# draft4_4lyr_autoroute.net
KiCad netlist of a schematic drawn in EAGLE
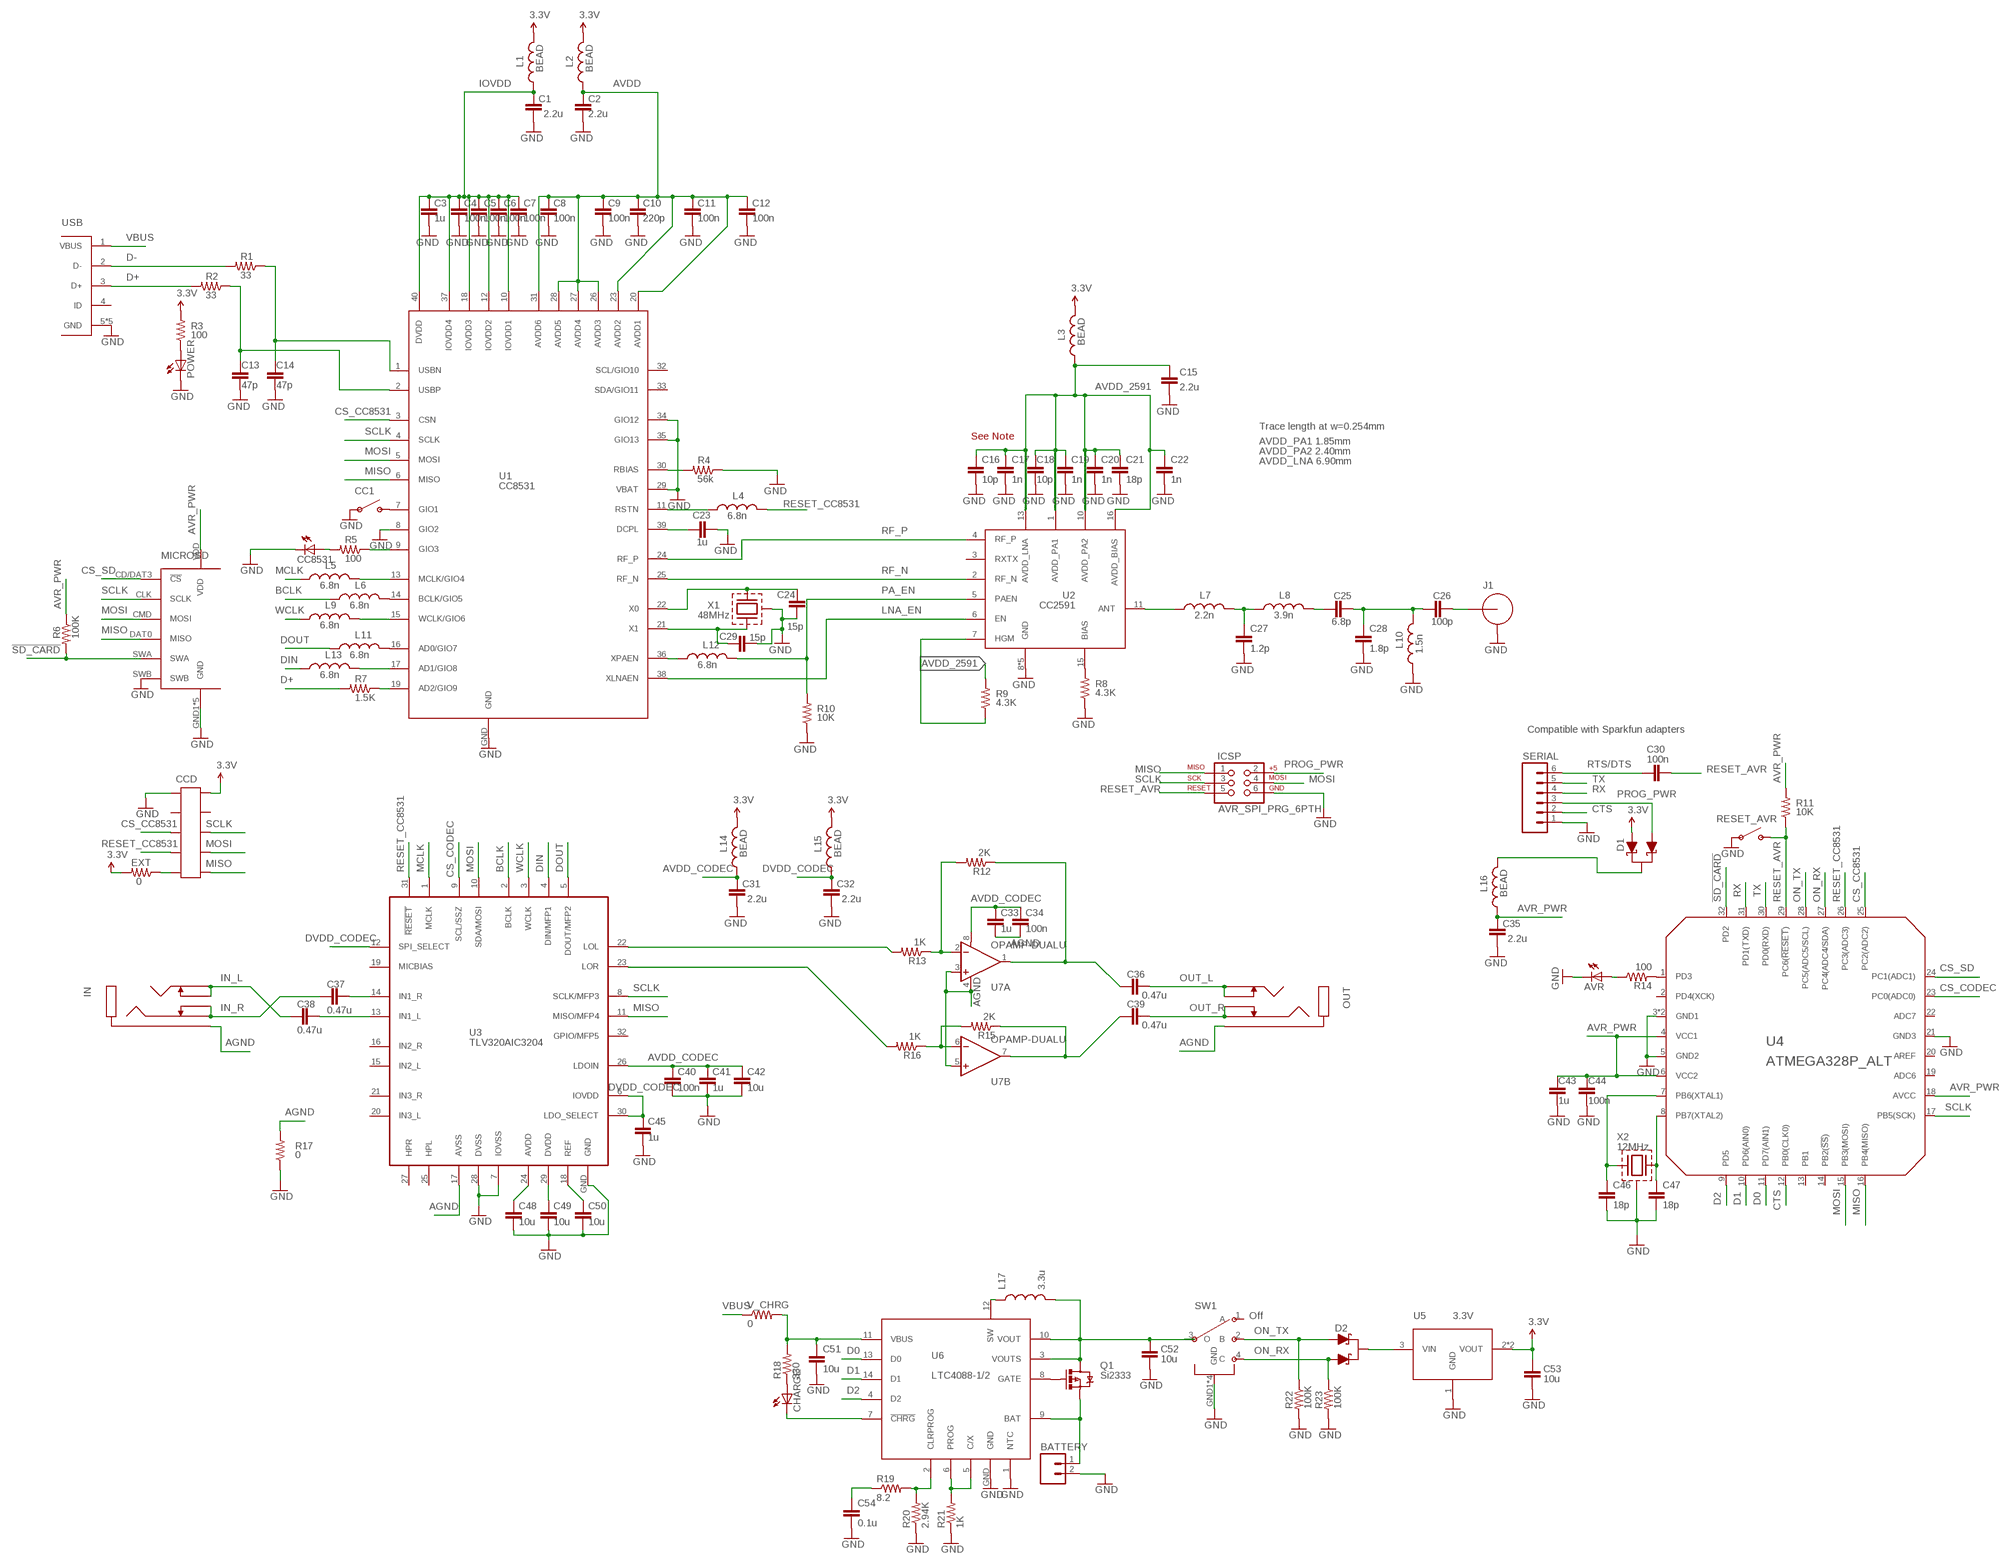
[diagram p0: schematic, sheet 1]

(export (version "E")
  (design (tool "Eeschema 10.0.6"))
  (components
    (comp (ref "AVR")
      (value "LED1206")
      (footprint "eagle-import:LED-1206")
      (libsource (lib "eagle-import") (part "LED1206"))
    )
    (comp (ref "BATTERY")
      (value "M02-JST-2MM-SMT")
      (footprint "eagle-import:JST-2-SMD")
      (libsource (lib "eagle-import") (part "M02-JST-2MM-SMT"))
    )
    (comp (ref "C1")
      (value "2.2u")
      (footprint "eagle-import:C0603")
      (libsource (lib "eagle-import") (part "rcl_C-EUC0603"))
    )
    (comp (ref "C2")
      (value "2.2u")
      (footprint "eagle-import:C0603")
      (libsource (lib "eagle-import") (part "rcl_C-EUC0603"))
    )
    (comp (ref "C3")
      (value "1u")
      (footprint "eagle-import:C0603")
      (libsource (lib "eagle-import") (part "rcl_C-EUC0603"))
    )
    (comp (ref "C4")
      (value "100n")
      (footprint "eagle-import:C0603")
      (libsource (lib "eagle-import") (part "rcl_C-EUC0603"))
    )
    (comp (ref "C5")
      (value "100n")
      (footprint "eagle-import:C0603")
      (libsource (lib "eagle-import") (part "rcl_C-EUC0603"))
    )
    (comp (ref "C6")
      (value "100n")
      (footprint "eagle-import:C0603")
      (libsource (lib "eagle-import") (part "rcl_C-EUC0603"))
    )
    (comp (ref "C7")
      (value "100n")
      (footprint "eagle-import:C0603")
      (libsource (lib "eagle-import") (part "rcl_C-EUC0603"))
    )
    (comp (ref "C8")
      (value "100n")
      (footprint "eagle-import:C0603")
      (libsource (lib "eagle-import") (part "rcl_C-EUC0603"))
    )
    (comp (ref "C9")
      (value "100n")
      (footprint "eagle-import:C0603")
      (libsource (lib "eagle-import") (part "rcl_C-EUC0603"))
    )
    (comp (ref "C10")
      (value "220p")
      (footprint "eagle-import:C0603")
      (libsource (lib "eagle-import") (part "rcl_C-EUC0603"))
    )
    (comp (ref "C11")
      (value "100n")
      (footprint "eagle-import:C0603")
      (libsource (lib "eagle-import") (part "rcl_C-EUC0603"))
    )
    (comp (ref "C12")
      (value "100n")
      (footprint "eagle-import:C0603")
      (libsource (lib "eagle-import") (part "rcl_C-EUC0603"))
    )
    (comp (ref "C13")
      (value "47p")
      (footprint "eagle-import:C0603")
      (libsource (lib "eagle-import") (part "rcl_C-EUC0603"))
    )
    (comp (ref "C14")
      (value "47p")
      (footprint "eagle-import:C0603")
      (libsource (lib "eagle-import") (part "rcl_C-EUC0603"))
    )
    (comp (ref "C15")
      (value "2.2u")
      (footprint "eagle-import:C0603")
      (libsource (lib "eagle-import") (part "rcl_C-EUC0603"))
    )
    (comp (ref "C16")
      (value "10p")
      (footprint "eagle-import:C0603")
      (libsource (lib "eagle-import") (part "rcl_C-EUC0603"))
    )
    (comp (ref "C17")
      (value "1n")
      (footprint "eagle-import:C0603")
      (libsource (lib "eagle-import") (part "rcl_C-EUC0603"))
    )
    (comp (ref "C18")
      (value "10p")
      (footprint "eagle-import:C0603")
      (libsource (lib "eagle-import") (part "rcl_C-EUC0603"))
    )
    (comp (ref "C19")
      (value "1n")
      (footprint "eagle-import:C0603")
      (libsource (lib "eagle-import") (part "rcl_C-EUC0603"))
    )
    (comp (ref "C20")
      (value "1n")
      (footprint "eagle-import:C0603")
      (libsource (lib "eagle-import") (part "rcl_C-EUC0603"))
    )
    (comp (ref "C21")
      (value "18p")
      (footprint "eagle-import:C0603")
      (libsource (lib "eagle-import") (part "rcl_C-EUC0603"))
    )
    (comp (ref "C22")
      (value "1n")
      (footprint "eagle-import:C0603")
      (libsource (lib "eagle-import") (part "rcl_C-EUC0603"))
    )
    (comp (ref "C23")
      (value "1u")
      (footprint "eagle-import:C0603")
      (libsource (lib "eagle-import") (part "rcl_C-EUC0603"))
    )
    (comp (ref "C24")
      (value "15p")
      (footprint "eagle-import:C0603")
      (libsource (lib "eagle-import") (part "rcl_C-EUC0603"))
    )
    (comp (ref "C25")
      (value "6.8p")
      (footprint "eagle-import:C0603")
      (libsource (lib "eagle-import") (part "rcl_C-EUC0603"))
    )
    (comp (ref "C26")
      (value "100p")
      (footprint "eagle-import:C0603")
      (libsource (lib "eagle-import") (part "rcl_C-EUC0603"))
    )
    (comp (ref "C27")
      (value "1.2p")
      (footprint "eagle-import:C0603")
      (libsource (lib "eagle-import") (part "rcl_C-EUC0603"))
    )
    (comp (ref "C28")
      (value "1.8p")
      (footprint "eagle-import:C0603")
      (libsource (lib "eagle-import") (part "rcl_C-EUC0603"))
    )
    (comp (ref "C29")
      (value "15p")
      (footprint "eagle-import:C0603")
      (libsource (lib "eagle-import") (part "rcl_C-EUC0603"))
    )
    (comp (ref "C30")
      (value "100n")
      (footprint "eagle-import:C0603")
      (libsource (lib "eagle-import") (part "rcl_C-EUC0603"))
    )
    (comp (ref "C31")
      (value "2.2u")
      (footprint "eagle-import:C0603")
      (libsource (lib "eagle-import") (part "rcl_C-EUC0603"))
    )
    (comp (ref "C32")
      (value "2.2u")
      (footprint "eagle-import:C0603")
      (libsource (lib "eagle-import") (part "rcl_C-EUC0603"))
    )
    (comp (ref "C33")
      (value "1u")
      (footprint "eagle-import:C0603")
      (libsource (lib "eagle-import") (part "rcl_C-EUC0603"))
    )
    (comp (ref "C34")
      (value "100n")
      (footprint "eagle-import:C0603")
      (libsource (lib "eagle-import") (part "rcl_C-EUC0603"))
    )
    (comp (ref "C35")
      (value "2.2u")
      (footprint "eagle-import:C0603")
      (libsource (lib "eagle-import") (part "rcl_C-EUC0603"))
    )
    (comp (ref "C36")
      (value "0.47u")
      (footprint "eagle-import:C0603")
      (libsource (lib "eagle-import") (part "rcl_C-EUC0603"))
    )
    (comp (ref "C37")
      (value "0.47u")
      (footprint "eagle-import:C0603")
      (libsource (lib "eagle-import") (part "rcl_C-EUC0603"))
    )
    (comp (ref "C38")
      (value "0.47u")
      (footprint "eagle-import:C0603")
      (libsource (lib "eagle-import") (part "rcl_C-EUC0603"))
    )
    (comp (ref "C39")
      (value "0.47u")
      (footprint "eagle-import:C0603")
      (libsource (lib "eagle-import") (part "rcl_C-EUC0603"))
    )
    (comp (ref "C40")
      (value "100n")
      (footprint "eagle-import:C0603")
      (libsource (lib "eagle-import") (part "rcl_C-EUC0603"))
    )
    (comp (ref "C41")
      (value "1u")
      (footprint "eagle-import:C0603")
      (libsource (lib "eagle-import") (part "rcl_C-EUC0603"))
    )
    (comp (ref "C42")
      (value "10u")
      (footprint "eagle-import:C0603")
      (libsource (lib "eagle-import") (part "rcl_C-EUC0603"))
    )
    (comp (ref "C43")
      (value "1u")
      (footprint "eagle-import:C0603")
      (libsource (lib "eagle-import") (part "rcl_C-EUC0603"))
    )
    (comp (ref "C44")
      (value "100n")
      (footprint "eagle-import:C0603")
      (libsource (lib "eagle-import") (part "rcl_C-EUC0603"))
    )
    (comp (ref "C45")
      (value "1u")
      (footprint "eagle-import:C0603")
      (libsource (lib "eagle-import") (part "rcl_C-EUC0603"))
    )
    (comp (ref "C46")
      (value "18p")
      (footprint "eagle-import:C0603")
      (libsource (lib "eagle-import") (part "C-EUC0603"))
    )
    (comp (ref "C47")
      (value "18p")
      (footprint "eagle-import:C0603")
      (libsource (lib "eagle-import") (part "C-EUC0603"))
    )
    (comp (ref "C48")
      (value "10u")
      (footprint "eagle-import:C0603")
      (libsource (lib "eagle-import") (part "rcl_C-EUC0603"))
    )
    (comp (ref "C49")
      (value "10u")
      (footprint "eagle-import:C0603")
      (libsource (lib "eagle-import") (part "rcl_C-EUC0603"))
    )
    (comp (ref "C50")
      (value "10u")
      (footprint "eagle-import:C0603")
      (libsource (lib "eagle-import") (part "rcl_C-EUC0603"))
    )
    (comp (ref "C51")
      (value "10u")
      (footprint "eagle-import:C0603")
      (libsource (lib "eagle-import") (part "C-EUC0603"))
    )
    (comp (ref "C52")
      (value "10u")
      (footprint "eagle-import:C0603")
      (libsource (lib "eagle-import") (part "rcl_C-EUC0603"))
    )
    (comp (ref "C53")
      (value "10u")
      (footprint "eagle-import:C0603")
      (libsource (lib "eagle-import") (part "rcl_C-EUC0603"))
    )
    (comp (ref "C54")
      (value "0.1u")
      (footprint "eagle-import:C0603")
      (libsource (lib "eagle-import") (part "C-EUC0603"))
    )
    (comp (ref "CC1")
      (value "SPST-SMD")
      (footprint "eagle-import:TACT_SW")
      (libsource (lib "eagle-import") (part "SPST-SMD"))
    )
    (comp (ref "CC8531")
      (value "LED1206")
      (footprint "eagle-import:LED-1206")
      (libsource (lib "eagle-import") (part "LED1206"))
    )
    (comp (ref "CCD")
      (value "HEADER-10P-PTH-MALE")
      (footprint "eagle-import:2X5")
      (libsource (lib "eagle-import") (part "HEADER-10P-PTH-MALE"))
    )
    (comp (ref "CHARGE")
      (value "LED1206")
      (footprint "eagle-import:LED-1206")
      (libsource (lib "eagle-import") (part "LED1206"))
    )
    (comp (ref "D1")
      (value "DUAL_SCHOTTKY")
      (footprint "eagle-import:SOT-23")
      (libsource (lib "eagle-import") (part "DUAL_SCHOTTKY"))
    )
    (comp (ref "D2")
      (value "DUAL_SCHOTTKY")
      (footprint "eagle-import:SOT-23")
      (libsource (lib "eagle-import") (part "DUAL_SCHOTTKY"))
    )
    (comp (ref "EXT")
      (value "0")
      (footprint "eagle-import:R0603")
      (libsource (lib "eagle-import") (part "rcl_R-US_R0603"))
    )
    (comp (ref "ICSP")
      (value "AVR_SPI_PRG_6PTH")
      (footprint "eagle-import:2X3")
      (libsource (lib "eagle-import") (part "AVR_SPI_PRG_6PTH"))
    )
    (comp (ref "IN")
      (value "PHONE_SW")
      (footprint "eagle-import:35RAPC4BV4")
      (libsource (lib "eagle-import") (part "PHONE_SW"))
    )
    (comp (ref "J1")
      (value "SMA")
      (footprint "eagle-import:CONSMA003.031")
      (libsource (lib "eagle-import") (part "SMA"))
    )
    (comp (ref "L1")
      (value "BEAD")
      (footprint "eagle-import:0603")
      (libsource (lib "eagle-import") (part "INDUCTOR0603"))
    )
    (comp (ref "L2")
      (value "BEAD")
      (footprint "eagle-import:0603")
      (libsource (lib "eagle-import") (part "INDUCTOR0603"))
    )
    (comp (ref "L3")
      (value "BEAD")
      (footprint "eagle-import:0603")
      (libsource (lib "eagle-import") (part "INDUCTOR0603"))
    )
    (comp (ref "L4")
      (value "6.8n")
      (footprint "eagle-import:0603")
      (libsource (lib "eagle-import") (part "INDUCTOR0603"))
    )
    (comp (ref "L5")
      (value "6.8n")
      (footprint "eagle-import:0603")
      (libsource (lib "eagle-import") (part "INDUCTOR0603"))
    )
    (comp (ref "L6")
      (value "6.8n")
      (footprint "eagle-import:0603")
      (libsource (lib "eagle-import") (part "INDUCTOR0603"))
    )
    (comp (ref "L7")
      (value "2.2n")
      (footprint "eagle-import:0603")
      (libsource (lib "eagle-import") (part "INDUCTOR0603"))
    )
    (comp (ref "L8")
      (value "3.9n")
      (footprint "eagle-import:0603")
      (libsource (lib "eagle-import") (part "INDUCTOR0603"))
    )
    (comp (ref "L9")
      (value "6.8n")
      (footprint "eagle-import:0603")
      (libsource (lib "eagle-import") (part "INDUCTOR0603"))
    )
    (comp (ref "L10")
      (value "1.5n")
      (footprint "eagle-import:0603")
      (libsource (lib "eagle-import") (part "INDUCTOR0603"))
    )
    (comp (ref "L11")
      (value "6.8n")
      (footprint "eagle-import:0603")
      (libsource (lib "eagle-import") (part "INDUCTOR0603"))
    )
    (comp (ref "L12")
      (value "6.8n")
      (footprint "eagle-import:0603")
      (libsource (lib "eagle-import") (part "INDUCTOR0603"))
    )
    (comp (ref "L13")
      (value "6.8n")
      (footprint "eagle-import:0603")
      (libsource (lib "eagle-import") (part "INDUCTOR0603"))
    )
    (comp (ref "L14")
      (value "BEAD")
      (footprint "eagle-import:0603")
      (libsource (lib "eagle-import") (part "INDUCTOR0603"))
    )
    (comp (ref "L15")
      (value "BEAD")
      (footprint "eagle-import:0603")
      (libsource (lib "eagle-import") (part "INDUCTOR0603"))
    )
    (comp (ref "L16")
      (value "BEAD")
      (footprint "eagle-import:0603")
      (libsource (lib "eagle-import") (part "INDUCTOR0603"))
    )
    (comp (ref "L17")
      (value "3.3u")
      (footprint "eagle-import:IFSC-1111AB-01")
      (libsource (lib "eagle-import") (part "IFSC-1111AB-01"))
    )
    (comp (ref "MICROSD")
      (value "MICROSD104031-0811")
      (footprint "eagle-import:MOLEX_104031-0811")
      (libsource (lib "eagle-import") (part "MICROSD104031-0811"))
    )
    (comp (ref "OUT")
      (value "PHONE_SW")
      (footprint "eagle-import:35RAPC4BV4")
      (libsource (lib "eagle-import") (part "PHONE_SW"))
    )
    (comp (ref "POWER")
      (value "LED1206")
      (footprint "eagle-import:LED-1206")
      (libsource (lib "eagle-import") (part "LED1206"))
    )
    (comp (ref "Q1")
      (value "Si2333")
      (footprint "eagle-import:SOT23-3")
      (libsource (lib "eagle-import") (part "MOSFET-PCHANNELSMD"))
    )
    (comp (ref "R1")
      (value "33")
      (footprint "eagle-import:R0603")
      (libsource (lib "eagle-import") (part "rcl_R-US_R0603"))
    )
    (comp (ref "R2")
      (value "33")
      (footprint "eagle-import:R0603")
      (libsource (lib "eagle-import") (part "rcl_R-US_R0603"))
    )
    (comp (ref "R3")
      (value "100")
      (footprint "eagle-import:R0603")
      (libsource (lib "eagle-import") (part "rcl_R-US_R0603"))
    )
    (comp (ref "R4")
      (value "56k")
      (footprint "eagle-import:R0603")
      (libsource (lib "eagle-import") (part "rcl_R-US_R0603"))
    )
    (comp (ref "R5")
      (value "100")
      (footprint "eagle-import:R0603")
      (libsource (lib "eagle-import") (part "rcl_R-US_R0603"))
    )
    (comp (ref "R6")
      (value "100K")
      (footprint "eagle-import:R0603")
      (libsource (lib "eagle-import") (part "rcl_R-US_R0603"))
    )
    (comp (ref "R7")
      (value "1.5K")
      (footprint "eagle-import:R0603")
      (libsource (lib "eagle-import") (part "rcl_R-US_R0603"))
    )
    (comp (ref "R8")
      (value "4.3K")
      (footprint "eagle-import:R0603")
      (libsource (lib "eagle-import") (part "rcl_R-US_R0603"))
    )
    (comp (ref "R9")
      (value "4.3K")
      (footprint "eagle-import:R0603")
      (libsource (lib "eagle-import") (part "rcl_R-US_R0603"))
    )
    (comp (ref "R10")
      (value "10K")
      (footprint "eagle-import:R0603")
      (libsource (lib "eagle-import") (part "rcl_R-US_R0603"))
    )
    (comp (ref "R11")
      (value "10K")
      (footprint "eagle-import:R0603")
      (libsource (lib "eagle-import") (part "rcl_R-US_R0603"))
    )
    (comp (ref "R12")
      (value "2K")
      (footprint "eagle-import:R0603")
      (libsource (lib "eagle-import") (part "R-US_R0603"))
    )
    (comp (ref "R13")
      (value "1K")
      (footprint "eagle-import:R0603")
      (libsource (lib "eagle-import") (part "R-US_R0603"))
    )
    (comp (ref "R14")
      (value "100")
      (footprint "eagle-import:R0603")
      (libsource (lib "eagle-import") (part "rcl_R-US_R0603"))
    )
    (comp (ref "R15")
      (value "2K")
      (footprint "eagle-import:R0603")
      (libsource (lib "eagle-import") (part "R-US_R0603"))
    )
    (comp (ref "R16")
      (value "1K")
      (footprint "eagle-import:R0603")
      (libsource (lib "eagle-import") (part "R-US_R0603"))
    )
    (comp (ref "R17")
      (value "0")
      (footprint "eagle-import:R0603")
      (libsource (lib "eagle-import") (part "rcl_R-US_R0603"))
    )
    (comp (ref "R18")
      (value "330")
      (footprint "eagle-import:R0603")
      (libsource (lib "eagle-import") (part "R-US_R0603"))
    )
    (comp (ref "R19")
      (value "8.2")
      (footprint "eagle-import:R0603")
      (libsource (lib "eagle-import") (part "R-US_R0603"))
    )
    (comp (ref "R20")
      (value "2.94K")
      (footprint "eagle-import:R0603")
      (libsource (lib "eagle-import") (part "R-US_R0603"))
    )
    (comp (ref "R21")
      (value "1K")
      (footprint "eagle-import:R0603")
      (libsource (lib "eagle-import") (part "R-US_R0603"))
    )
    (comp (ref "R22")
      (value "100K")
      (footprint "eagle-import:R0603")
      (libsource (lib "eagle-import") (part "rcl_R-US_R0603"))
    )
    (comp (ref "R23")
      (value "100K")
      (footprint "eagle-import:R0603")
      (libsource (lib "eagle-import") (part "rcl_R-US_R0603"))
    )
    (comp (ref "RESET_AVR")
      (value "SPST-SMD")
      (footprint "eagle-import:TACT_SW")
      (libsource (lib "eagle-import") (part "SPST-SMD"))
    )
    (comp (ref "SERIAL")
      (value "M06SIP")
      (footprint "eagle-import:1X06")
      (libsource (lib "eagle-import") (part "M06SIP"))
    )
    (comp (ref "SW1")
      (value "SP3T-SSSS812201")
      (footprint "eagle-import:SSSS812201")
      (libsource (lib "eagle-import") (part "SP3T-SSSS812201"))
    )
    (comp (ref "U1")
      (value "CC8531")
      (footprint "eagle-import:S-PVQFN-N40")
      (libsource (lib "eagle-import") (part "CC8531"))
    )
    (comp (ref "U2")
      (value "CC2591")
      (footprint "eagle-import:S-PVQFN-N16")
      (libsource (lib "eagle-import") (part "CC2591"))
    )
    (comp (ref "U3")
      (value "TLV320AIC3204")
      (footprint "eagle-import:S-PVQFN-N32")
      (libsource (lib "eagle-import") (part "TLV320AIC3204"))
    )
    (comp (ref "U4")
      (value "ATMEGA328P_ALT")
      (footprint "eagle-import:S-PQFP-N32")
      (libsource (lib "eagle-import") (part "ATMEGA328P_ALT"))
    )
    (comp (ref "U5")
      (value "3.3V")
      (footprint "eagle-import:SOT-223")
      (libsource (lib "eagle-import") (part "NX1117C"))
    )
    (comp (ref "U6")
      (value "LTC4088-1/2")
      (footprint "eagle-import:DFN-14")
      (libsource (lib "eagle-import") (part "LTC4088-1/2"))
    )
    (comp (ref "U7")
      (value "OPAMP-DUALU")
      (footprint "eagle-import:SO08")
      (libsource (lib "eagle-import") (part "OPAMP-DUALU"))
    )
    (comp (ref "USB")
      (value "USB_MICRO_AB")
      (footprint "eagle-import:USB_MICRO_AB")
      (libsource (lib "eagle-import") (part "USB_MICRO_AB"))
    )
    (comp (ref "V_CHRG")
      (value "0")
      (footprint "eagle-import:R0603")
      (libsource (lib "eagle-import") (part "R-US_R0603"))
    )
    (comp (ref "X1")
      (value "48MHz")
      (footprint "eagle-import:ABM3C")
      (libsource (lib "eagle-import") (part "XTAL-ABRACONABM3C"))
    )
    (comp (ref "X2")
      (value "12MHz")
      (footprint "eagle-import:ABM8G")
      (libsource (lib "eagle-import") (part "XTAL-ABRACONABM8G"))
    )
  )
  (nets
    (net (code "1") (name "/AGND") (class "Default")
      (node (ref "C33") (pin "2") (pinfunction "2_2") (pintype "passive"))
      (node (ref "C34") (pin "2") (pinfunction "2_2") (pintype "passive"))
      (node (ref "IN") (pin "1") (pinfunction "GND_1") (pintype "bidirectional"))
      (node (ref "OUT") (pin "1") (pinfunction "GND_1") (pintype "bidirectional"))
      (node (ref "R17") (pin "2") (pinfunction "2_2") (pintype "passive"))
      (node (ref "U3") (pin "17") (pinfunction "AVSS_17") (pintype "bidirectional"))
      (node (ref "U7") (pin "3") (pinfunction "+IN_3") (pintype "input"))
      (node (ref "U7") (pin "4") (pinfunction "V-_4") (pintype "power_in"))
      (node (ref "U7") (pin "5") (pinfunction "+IN_5") (pintype "input"))
    )
    (net (code "2") (name "/AVDD") (class "Default")
      (node (ref "C10") (pin "1") (pinfunction "1_1") (pintype "passive"))
      (node (ref "C11") (pin "1") (pinfunction "1_1") (pintype "passive"))
      (node (ref "C12") (pin "1") (pinfunction "1_1") (pintype "passive"))
      (node (ref "C2") (pin "1") (pinfunction "1_1") (pintype "passive"))
      (node (ref "C8") (pin "1") (pinfunction "1_1") (pintype "passive"))
      (node (ref "C9") (pin "1") (pinfunction "1_1") (pintype "passive"))
      (node (ref "L2") (pin "1") (pinfunction "1_1") (pintype "passive"))
      (node (ref "U1") (pin "20") (pinfunction "AVDD1_20") (pintype "bidirectional"))
      (node (ref "U1") (pin "23") (pinfunction "AVDD2_23") (pintype "bidirectional"))
      (node (ref "U1") (pin "26") (pinfunction "AVDD3_26") (pintype "bidirectional"))
      (node (ref "U1") (pin "27") (pinfunction "AVDD4_27") (pintype "bidirectional"))
      (node (ref "U1") (pin "28") (pinfunction "AVDD5_28") (pintype "bidirectional"))
      (node (ref "U1") (pin "31") (pinfunction "AVDD6_31") (pintype "bidirectional"))
    )
    (net (code "3") (name "/AVDD_CODEC") (class "Default")
      (node (ref "C31") (pin "1") (pinfunction "1_1") (pintype "passive"))
      (node (ref "C33") (pin "1") (pinfunction "1_1") (pintype "passive"))
      (node (ref "C34") (pin "1") (pinfunction "1_1") (pintype "passive"))
      (node (ref "C40") (pin "1") (pinfunction "1_1") (pintype "passive"))
      (node (ref "C41") (pin "1") (pinfunction "1_1") (pintype "passive"))
      (node (ref "C42") (pin "1") (pinfunction "1_1") (pintype "passive"))
      (node (ref "L14") (pin "1") (pinfunction "1_1") (pintype "passive"))
      (node (ref "U3") (pin "26") (pinfunction "LDOIN_26") (pintype "bidirectional"))
      (node (ref "U7") (pin "8") (pinfunction "V+_8") (pintype "power_in"))
    )
    (net (code "4") (name "/AVR_PWR") (class "Default")
      (node (ref "C35") (pin "1") (pinfunction "1_1") (pintype "passive"))
      (node (ref "C43") (pin "1") (pinfunction "1_1") (pintype "passive"))
      (node (ref "C44") (pin "1") (pinfunction "1_1") (pintype "passive"))
      (node (ref "L16") (pin "1") (pinfunction "1_1") (pintype "passive"))
      (node (ref "MICROSD") (pin "VDD") (pinfunction "VDD_VDD") (pintype "bidirectional"))
      (node (ref "R11") (pin "2") (pinfunction "2_2") (pintype "passive"))
      (node (ref "R6") (pin "1") (pinfunction "1_1") (pintype "passive"))
      (node (ref "U4") (pin "18") (pinfunction "AVCC_18") (pintype "bidirectional"))
      (node (ref "U4") (pin "4") (pinfunction "VCC1_4") (pintype "bidirectional"))
      (node (ref "U4") (pin "6") (pinfunction "VCC2_6") (pintype "bidirectional"))
    )
    (net (code "5") (name "/BCLK") (class "Default")
      (node (ref "L6") (pin "1") (pinfunction "1_1") (pintype "passive"))
      (node (ref "U3") (pin "2") (pinfunction "BCLK_2") (pintype "bidirectional"))
    )
    (net (code "6") (name "/CS_CC8531") (class "Default")
      (node (ref "CCD") (pin "5") (pinfunction "5_5") (pintype "bidirectional"))
      (node (ref "U1") (pin "3") (pinfunction "CSN_3") (pintype "bidirectional"))
      (node (ref "U4") (pin "25") (pinfunction "PC2(ADC2)_25") (pintype "bidirectional"))
    )
    (net (code "7") (name "/CS_CODEC") (class "Default")
      (node (ref "U3") (pin "9") (pinfunction "SCL/SSZ_9") (pintype "bidirectional"))
      (node (ref "U4") (pin "23") (pinfunction "PC0(ADC0)_23") (pintype "bidirectional"))
    )
    (net (code "8") (name "/CS_SD") (class "Default")
      (node (ref "MICROSD") (pin "CD/DAT3") (pinfunction "~{CS}_CD/DAT3") (pintype "bidirectional"))
      (node (ref "U4") (pin "24") (pinfunction "PC1(ADC1)_24") (pintype "bidirectional"))
    )
    (net (code "9") (name "/CTS") (class "Default")
      (node (ref "SERIAL") (pin "2") (pinfunction "2_2") (pintype "passive"))
      (node (ref "U4") (pin "12") (pinfunction "PB0(CLK0)_12") (pintype "bidirectional"))
    )
    (net (code "10") (name "/D+") (class "Default")
      (node (ref "R2") (pin "2") (pinfunction "2_2") (pintype "passive"))
      (node (ref "R7") (pin "2") (pinfunction "2_2") (pintype "passive"))
      (node (ref "USB") (pin "3") (pinfunction "D+_3") (pintype "bidirectional"))
    )
    (net (code "11") (name "/D-") (class "Default")
      (node (ref "R1") (pin "2") (pinfunction "2_2") (pintype "passive"))
      (node (ref "USB") (pin "2") (pinfunction "D-_2") (pintype "bidirectional"))
    )
    (net (code "12") (name "/D0") (class "Default")
      (node (ref "U4") (pin "11") (pinfunction "PD7(AIN1)_11") (pintype "bidirectional"))
      (node (ref "U6") (pin "13") (pinfunction "D0_13") (pintype "bidirectional"))
    )
    (net (code "13") (name "/D1") (class "Default")
      (node (ref "U4") (pin "10") (pinfunction "PD6(AIN0)_10") (pintype "bidirectional"))
      (node (ref "U6") (pin "14") (pinfunction "D1_14") (pintype "bidirectional"))
    )
    (net (code "14") (name "/D2") (class "Default")
      (node (ref "U4") (pin "9") (pinfunction "PD5_9") (pintype "bidirectional"))
      (node (ref "U6") (pin "4") (pinfunction "D2_4") (pintype "bidirectional"))
    )
    (net (code "15") (name "/DIN") (class "Default")
      (node (ref "L13") (pin "1") (pinfunction "1_1") (pintype "passive"))
      (node (ref "U3") (pin "4") (pinfunction "DIN/MFP1_4") (pintype "bidirectional"))
    )
    (net (code "16") (name "/DOUT") (class "Default")
      (node (ref "L11") (pin "1") (pinfunction "1_1") (pintype "passive"))
      (node (ref "U3") (pin "5") (pinfunction "DOUT/MFP2_5") (pintype "bidirectional"))
    )
    (net (code "17") (name "/DVDD_CODEC") (class "Default")
      (node (ref "C32") (pin "1") (pinfunction "1_1") (pintype "passive"))
      (node (ref "C45") (pin "1") (pinfunction "1_1") (pintype "passive"))
      (node (ref "L15") (pin "1") (pinfunction "1_1") (pintype "passive"))
      (node (ref "U3") (pin "12") (pinfunction "SPI_SELECT_12") (pintype "bidirectional"))
      (node (ref "U3") (pin "30") (pinfunction "LDO_SELECT_30") (pintype "bidirectional"))
      (node (ref "U3") (pin "6") (pinfunction "IOVDD_6") (pintype "bidirectional"))
    )
    (net (code "18") (name "/IN_L") (class "Default")
      (node (ref "C38") (pin "1") (pinfunction "1_1") (pintype "passive"))
      (node (ref "IN") (pin "2") (pinfunction "L_2") (pintype "bidirectional"))
      (node (ref "IN") (pin "5") (pinfunction "L_SW_5") (pintype "bidirectional"))
    )
    (net (code "19") (name "/IN_R") (class "Default")
      (node (ref "C37") (pin "1") (pinfunction "1_1") (pintype "passive"))
      (node (ref "IN") (pin "3") (pinfunction "R_SW_3") (pintype "bidirectional"))
      (node (ref "IN") (pin "4") (pinfunction "R_4") (pintype "bidirectional"))
    )
    (net (code "20") (name "/IOVDD") (class "Default")
      (node (ref "C1") (pin "1") (pinfunction "1_1") (pintype "passive"))
      (node (ref "C3") (pin "1") (pinfunction "1_1") (pintype "passive"))
      (node (ref "C4") (pin "1") (pinfunction "1_1") (pintype "passive"))
      (node (ref "C5") (pin "1") (pinfunction "1_1") (pintype "passive"))
      (node (ref "C6") (pin "1") (pinfunction "1_1") (pintype "passive"))
      (node (ref "C7") (pin "1") (pinfunction "1_1") (pintype "passive"))
      (node (ref "L1") (pin "1") (pinfunction "1_1") (pintype "passive"))
      (node (ref "U1") (pin "10") (pinfunction "IOVDD1_10") (pintype "bidirectional"))
      (node (ref "U1") (pin "12") (pinfunction "IOVDD2_12") (pintype "bidirectional"))
      (node (ref "U1") (pin "18") (pinfunction "IOVDD3_18") (pintype "bidirectional"))
      (node (ref "U1") (pin "37") (pinfunction "IOVDD4_37") (pintype "bidirectional"))
      (node (ref "U1") (pin "40") (pinfunction "DVDD_40") (pintype "bidirectional"))
    )
    (net (code "21") (name "/LNA_EN") (class "Default")
      (node (ref "U1") (pin "38") (pinfunction "XLNAEN_38") (pintype "bidirectional"))
      (node (ref "U2") (pin "6") (pinfunction "EN_6") (pintype "bidirectional"))
    )
    (net (code "22") (name "/MCLK") (class "Default")
      (node (ref "L5") (pin "1") (pinfunction "1_1") (pintype "passive"))
      (node (ref "U3") (pin "1") (pinfunction "MCLK_1") (pintype "bidirectional"))
    )
    (net (code "23") (name "/MISO") (class "Default")
      (node (ref "CCD") (pin "10") (pinfunction "10_10") (pintype "bidirectional"))
      (node (ref "ICSP") (pin "1") (pinfunction "1_1") (pintype "passive"))
      (node (ref "MICROSD") (pin "DAT0") (pinfunction "MISO_DAT0") (pintype "bidirectional"))
      (node (ref "U1") (pin "6") (pinfunction "MISO_6") (pintype "bidirectional"))
      (node (ref "U3") (pin "11") (pinfunction "MISO/MFP4_11") (pintype "bidirectional"))
      (node (ref "U4") (pin "16") (pinfunction "PB4(MISO)_16") (pintype "bidirectional"))
    )
    (net (code "24") (name "/MOSI") (class "Default")
      (node (ref "CCD") (pin "8") (pinfunction "8_8") (pintype "bidirectional"))
      (node (ref "ICSP") (pin "4") (pinfunction "4_4") (pintype "passive"))
      (node (ref "MICROSD") (pin "CMD") (pinfunction "MOSI_CMD") (pintype "bidirectional"))
      (node (ref "U1") (pin "5") (pinfunction "MOSI_5") (pintype "bidirectional"))
      (node (ref "U3") (pin "10") (pinfunction "SDA/MOSI_10") (pintype "bidirectional"))
      (node (ref "U4") (pin "15") (pinfunction "PB3(MOSI)_15") (pintype "bidirectional"))
    )
    (net (code "25") (name "/ON_RX") (class "Default")
      (node (ref "D2") (pin "2") (pinfunction "A_2") (pintype "passive"))
      (node (ref "R23") (pin "1") (pinfunction "1_1") (pintype "passive"))
      (node (ref "SW1") (pin "4") (pinfunction "C_4") (pintype "bidirectional"))
      (node (ref "U4") (pin "27") (pinfunction "PC4(ADC4/SDA)_27") (pintype "bidirectional"))
    )
    (net (code "26") (name "/ON_TX") (class "Default")
      (node (ref "D2") (pin "1") (pinfunction "A1_1") (pintype "passive"))
      (node (ref "R22") (pin "1") (pinfunction "1_1") (pintype "passive"))
      (node (ref "SW1") (pin "2") (pinfunction "B_2") (pintype "bidirectional"))
      (node (ref "U4") (pin "28") (pinfunction "PC5(ADC5/SCL)_28") (pintype "bidirectional"))
    )
    (net (code "27") (name "/OUT_L") (class "Default")
      (node (ref "C36") (pin "2") (pinfunction "2_2") (pintype "passive"))
      (node (ref "OUT") (pin "2") (pinfunction "L_2") (pintype "bidirectional"))
      (node (ref "OUT") (pin "5") (pinfunction "L_SW_5") (pintype "bidirectional"))
    )
    (net (code "28") (name "/OUT_R") (class "Default")
      (node (ref "C39") (pin "2") (pinfunction "2_2") (pintype "passive"))
      (node (ref "OUT") (pin "3") (pinfunction "R_SW_3") (pintype "bidirectional"))
      (node (ref "OUT") (pin "4") (pinfunction "R_4") (pintype "bidirectional"))
    )
    (net (code "29") (name "/PA_EN") (class "Default")
      (node (ref "L12") (pin "2") (pinfunction "2_2") (pintype "passive"))
      (node (ref "R10") (pin "2") (pinfunction "2_2") (pintype "passive"))
      (node (ref "U2") (pin "5") (pinfunction "PAEN_5") (pintype "bidirectional"))
    )
    (net (code "30") (name "/PROG_PWR") (class "Default")
      (node (ref "D1") (pin "2") (pinfunction "A_2") (pintype "passive"))
      (node (ref "ICSP") (pin "2") (pinfunction "2_2") (pintype "passive"))
      (node (ref "SERIAL") (pin "3") (pinfunction "3_3") (pintype "passive"))
    )
    (net (code "31") (name "/RESET_AVR") (class "Default")
      (node (ref "C30") (pin "2") (pinfunction "2_2") (pintype "passive"))
      (node (ref "ICSP") (pin "5") (pinfunction "5_5") (pintype "passive"))
      (node (ref "R11") (pin "1") (pinfunction "1_1") (pintype "passive"))
      (node (ref "RESET_AVR") (pin "3") (pinfunction "P$2_3") (pintype "bidirectional"))
      (node (ref "RESET_AVR") (pin "4") (pinfunction "P$2_4") (pintype "bidirectional"))
      (node (ref "U4") (pin "29") (pinfunction "PC6(~{RESET})_29") (pintype "bidirectional"))
    )
    (net (code "32") (name "/RESET_CC8531") (class "Default")
      (node (ref "CCD") (pin "7") (pinfunction "7_7") (pintype "bidirectional"))
      (node (ref "L4") (pin "2") (pinfunction "2_2") (pintype "passive"))
      (node (ref "U3") (pin "31") (pinfunction "~{RESET}_31") (pintype "bidirectional"))
      (node (ref "U4") (pin "26") (pinfunction "PC3(ADC3)_26") (pintype "bidirectional"))
    )
    (net (code "33") (name "/RF_N") (class "Default")
      (node (ref "U1") (pin "25") (pinfunction "RF_N_25") (pintype "bidirectional"))
      (node (ref "U2") (pin "2") (pinfunction "RF_N_2") (pintype "bidirectional"))
    )
    (net (code "34") (name "/RF_P") (class "Default")
      (node (ref "U1") (pin "24") (pinfunction "RF_P_24") (pintype "bidirectional"))
      (node (ref "U2") (pin "4") (pinfunction "RF_P_4") (pintype "bidirectional"))
    )
    (net (code "35") (name "/RTS{slash}DTS") (class "Default")
      (node (ref "C30") (pin "1") (pinfunction "1_1") (pintype "passive"))
      (node (ref "SERIAL") (pin "6") (pinfunction "6_6") (pintype "passive"))
    )
    (net (code "36") (name "/RX") (class "Default")
      (node (ref "SERIAL") (pin "4") (pinfunction "4_4") (pintype "passive"))
      (node (ref "U4") (pin "31") (pinfunction "PD1(TXD)_31") (pintype "bidirectional"))
    )
    (net (code "37") (name "/SCLK") (class "Default")
      (node (ref "CCD") (pin "6") (pinfunction "6_6") (pintype "bidirectional"))
      (node (ref "ICSP") (pin "3") (pinfunction "3_3") (pintype "passive"))
      (node (ref "MICROSD") (pin "CLK") (pinfunction "SCLK_CLK") (pintype "bidirectional"))
      (node (ref "U1") (pin "4") (pinfunction "SCLK_4") (pintype "bidirectional"))
      (node (ref "U3") (pin "8") (pinfunction "SCLK/MFP3_8") (pintype "bidirectional"))
      (node (ref "U4") (pin "17") (pinfunction "PB5(SCK)_17") (pintype "bidirectional"))
    )
    (net (code "38") (name "/TX") (class "Default")
      (node (ref "SERIAL") (pin "5") (pinfunction "5_5") (pintype "passive"))
      (node (ref "U4") (pin "30") (pinfunction "PD0(RXD)_30") (pintype "bidirectional"))
    )
    (net (code "39") (name "/VBUS") (class "Default")
      (node (ref "USB") (pin "1") (pinfunction "VBUS_1") (pintype "bidirectional"))
      (node (ref "V_CHRG") (pin "1") (pinfunction "1_1") (pintype "passive"))
    )
    (net (code "40") (name "/WCLK") (class "Default")
      (node (ref "L9") (pin "1") (pinfunction "1_1") (pintype "passive"))
      (node (ref "U3") (pin "3") (pinfunction "WCLK_3") (pintype "bidirectional"))
    )
    (net (code "41") (name "/~{SD_CARD}") (class "Default")
      (node (ref "MICROSD") (pin "SWA") (pinfunction "SWA_SWA") (pintype "bidirectional"))
      (node (ref "R6") (pin "2") (pinfunction "2_2") (pintype "passive"))
      (node (ref "U4") (pin "32") (pinfunction "PD2_32") (pintype "bidirectional"))
    )
    (net (code "42") (name "3.3V") (class "Default")
      (node (ref "C53") (pin "1") (pinfunction "1_1") (pintype "passive"))
      (node (ref "CCD") (pin "2") (pinfunction "2_2") (pintype "bidirectional"))
      (node (ref "D1") (pin "1") (pinfunction "A1_1") (pintype "passive"))
      (node (ref "EXT") (pin "2") (pinfunction "2_2") (pintype "passive"))
      (node (ref "L1") (pin "2") (pinfunction "2_2") (pintype "passive"))
      (node (ref "L14") (pin "2") (pinfunction "2_2") (pintype "passive"))
      (node (ref "L15") (pin "2") (pinfunction "2_2") (pintype "passive"))
      (node (ref "L2") (pin "2") (pinfunction "2_2") (pintype "passive"))
      (node (ref "L3") (pin "2") (pinfunction "2_2") (pintype "passive"))
      (node (ref "R3") (pin "2") (pinfunction "2_2") (pintype "passive"))
      (node (ref "U5") (pin "2") (pinfunction "VOUT_2") (pintype "bidirectional"))
      (node (ref "U5") (pin "4") (pinfunction "VOUT_4") (pintype "bidirectional"))
    )
    (net (code "43") (name "AVDD_2591") (class "Default")
      (node (ref "C15") (pin "1") (pinfunction "1_1") (pintype "passive"))
      (node (ref "C16") (pin "1") (pinfunction "1_1") (pintype "passive"))
      (node (ref "C17") (pin "1") (pinfunction "1_1") (pintype "passive"))
      (node (ref "C18") (pin "1") (pinfunction "1_1") (pintype "passive"))
      (node (ref "C19") (pin "1") (pinfunction "1_1") (pintype "passive"))
      (node (ref "C20") (pin "1") (pinfunction "1_1") (pintype "passive"))
      (node (ref "C21") (pin "1") (pinfunction "1_1") (pintype "passive"))
      (node (ref "C22") (pin "1") (pinfunction "1_1") (pintype "passive"))
      (node (ref "L3") (pin "1") (pinfunction "1_1") (pintype "passive"))
      (node (ref "R9") (pin "2") (pinfunction "2_2") (pintype "passive"))
      (node (ref "U2") (pin "1") (pinfunction "AVDD_PA1_1") (pintype "bidirectional"))
      (node (ref "U2") (pin "10") (pinfunction "AVDD_PA2_10") (pintype "bidirectional"))
      (node (ref "U2") (pin "13") (pinfunction "AVDD_LNA_13") (pintype "bidirectional"))
      (node (ref "U2") (pin "16") (pinfunction "AVDD_BIAS_16") (pintype "bidirectional"))
    )
    (net (code "44") (name "GND") (class "Default")
      (node (ref "AVR") (pin "C") (pinfunction "C_C") (pintype "passive"))
      (node (ref "BATTERY") (pin "2") (pinfunction "1_2") (pintype "passive"))
      (node (ref "C1") (pin "2") (pinfunction "2_2") (pintype "passive"))
      (node (ref "C10") (pin "2") (pinfunction "2_2") (pintype "passive"))
      (node (ref "C11") (pin "2") (pinfunction "2_2") (pintype "passive"))
      (node (ref "C12") (pin "2") (pinfunction "2_2") (pintype "passive"))
      (node (ref "C13") (pin "2") (pinfunction "2_2") (pintype "passive"))
      (node (ref "C14") (pin "2") (pinfunction "2_2") (pintype "passive"))
      (node (ref "C15") (pin "2") (pinfunction "2_2") (pintype "passive"))
      (node (ref "C16") (pin "2") (pinfunction "2_2") (pintype "passive"))
      (node (ref "C17") (pin "2") (pinfunction "2_2") (pintype "passive"))
      (node (ref "C18") (pin "2") (pinfunction "2_2") (pintype "passive"))
      (node (ref "C19") (pin "2") (pinfunction "2_2") (pintype "passive"))
      (node (ref "C2") (pin "2") (pinfunction "2_2") (pintype "passive"))
      (node (ref "C20") (pin "2") (pinfunction "2_2") (pintype "passive"))
      (node (ref "C21") (pin "2") (pinfunction "2_2") (pintype "passive"))
      (node (ref "C22") (pin "2") (pinfunction "2_2") (pintype "passive"))
      (node (ref "C23") (pin "2") (pinfunction "2_2") (pintype "passive"))
      (node (ref "C24") (pin "2") (pinfunction "2_2") (pintype "passive"))
      (node (ref "C27") (pin "2") (pinfunction "2_2") (pintype "passive"))
      (node (ref "C28") (pin "2") (pinfunction "2_2") (pintype "passive"))
      (node (ref "C29") (pin "2") (pinfunction "2_2") (pintype "passive"))
      (node (ref "C3") (pin "2") (pinfunction "2_2") (pintype "passive"))
      (node (ref "C31") (pin "2") (pinfunction "2_2") (pintype "passive"))
      (node (ref "C32") (pin "2") (pinfunction "2_2") (pintype "passive"))
      (node (ref "C35") (pin "2") (pinfunction "2_2") (pintype "passive"))
      (node (ref "C4") (pin "2") (pinfunction "2_2") (pintype "passive"))
      (node (ref "C40") (pin "2") (pinfunction "2_2") (pintype "passive"))
      (node (ref "C41") (pin "2") (pinfunction "2_2") (pintype "passive"))
      (node (ref "C42") (pin "2") (pinfunction "2_2") (pintype "passive"))
      (node (ref "C43") (pin "2") (pinfunction "2_2") (pintype "passive"))
      (node (ref "C44") (pin "2") (pinfunction "2_2") (pintype "passive"))
      (node (ref "C45") (pin "2") (pinfunction "2_2") (pintype "passive"))
      (node (ref "C46") (pin "2") (pinfunction "2_2") (pintype "passive"))
      (node (ref "C47") (pin "2") (pinfunction "2_2") (pintype "passive"))
      (node (ref "C48") (pin "2") (pinfunction "2_2") (pintype "passive"))
      (node (ref "C49") (pin "2") (pinfunction "2_2") (pintype "passive"))
      (node (ref "C5") (pin "2") (pinfunction "2_2") (pintype "passive"))
      (node (ref "C50") (pin "2") (pinfunction "2_2") (pintype "passive"))
      (node (ref "C51") (pin "2") (pinfunction "2_2") (pintype "passive"))
      (node (ref "C52") (pin "2") (pinfunction "2_2") (pintype "passive"))
      (node (ref "C53") (pin "2") (pinfunction "2_2") (pintype "passive"))
      (node (ref "C54") (pin "2") (pinfunction "2_2") (pintype "passive"))
      (node (ref "C6") (pin "2") (pinfunction "2_2") (pintype "passive"))
      (node (ref "C7") (pin "2") (pinfunction "2_2") (pintype "passive"))
      (node (ref "C8") (pin "2") (pinfunction "2_2") (pintype "passive"))
      (node (ref "C9") (pin "2") (pinfunction "2_2") (pintype "passive"))
      (node (ref "CC1") (pin "1") (pinfunction "P$1_1") (pintype "bidirectional"))
      (node (ref "CC1") (pin "2") (pinfunction "P$1_2") (pintype "bidirectional"))
      (node (ref "CC8531") (pin "C") (pinfunction "C_C") (pintype "passive"))
      (node (ref "CCD") (pin "1") (pinfunction "1_1") (pintype "bidirectional"))
      (node (ref "ICSP") (pin "6") (pinfunction "6_6") (pintype "passive"))
      (node (ref "J1") (pin "GND1") (pinfunction "GND_GND1") (pintype "bidirectional"))
      (node (ref "J1") (pin "GND2") (pinfunction "GND_GND2") (pintype "bidirectional"))
      (node (ref "J1") (pin "GND3") (pinfunction "GND_GND3") (pintype "bidirectional"))
      (node (ref "J1") (pin "GND4") (pinfunction "GND_GND4") (pintype "bidirectional"))
      (node (ref "L10") (pin "1") (pinfunction "1_1") (pintype "passive"))
      (node (ref "MICROSD") (pin "GND1") (pinfunction "GND_GND1") (pintype "bidirectional"))
      (node (ref "MICROSD") (pin "GND2") (pinfunction "GND_GND2") (pintype "bidirectional"))
      (node (ref "MICROSD") (pin "GND3") (pinfunction "GND_GND3") (pintype "bidirectional"))
      (node (ref "MICROSD") (pin "GND4") (pinfunction "GND_GND4") (pintype "bidirectional"))
      (node (ref "MICROSD") (pin "SWB") (pinfunction "SWB_SWB") (pintype "bidirectional"))
      (node (ref "MICROSD") (pin "VSS") (pinfunction "GND_VSS") (pintype "bidirectional"))
      (node (ref "POWER") (pin "C") (pinfunction "C_C") (pintype "passive"))
      (node (ref "R10") (pin "1") (pinfunction "1_1") (pintype "passive"))
      (node (ref "R17") (pin "1") (pinfunction "1_1") (pintype "passive"))
      (node (ref "R20") (pin "1") (pinfunction "1_1") (pintype "passive"))
      (node (ref "R21") (pin "1") (pinfunction "1_1") (pintype "passive"))
      (node (ref "R22") (pin "2") (pinfunction "2_2") (pintype "passive"))
      (node (ref "R23") (pin "2") (pinfunction "2_2") (pintype "passive"))
      (node (ref "R4") (pin "1") (pinfunction "1_1") (pintype "passive"))
      (node (ref "R8") (pin "1") (pinfunction "1_1") (pintype "passive"))
      (node (ref "RESET_AVR") (pin "1") (pinfunction "P$1_1") (pintype "bidirectional"))
      (node (ref "RESET_AVR") (pin "2") (pinfunction "P$1_2") (pintype "bidirectional"))
      (node (ref "SERIAL") (pin "1") (pinfunction "1_1") (pintype "passive"))
      (node (ref "SW1") (pin "GND1") (pinfunction "GND_GND1") (pintype "bidirectional"))
      (node (ref "SW1") (pin "GND2") (pinfunction "GND_GND2") (pintype "bidirectional"))
      (node (ref "SW1") (pin "GND3") (pinfunction "GND_GND3") (pintype "bidirectional"))
      (node (ref "SW1") (pin "GND4") (pinfunction "GND_GND4") (pintype "bidirectional"))
      (node (ref "U1") (pin "29") (pinfunction "VBAT_29") (pintype "bidirectional"))
      (node (ref "U1") (pin "34") (pinfunction "GIO12_34") (pintype "bidirectional"))
      (node (ref "U1") (pin "35") (pinfunction "GIO13_35") (pintype "bidirectional"))
      (node (ref "U1") (pin "8") (pinfunction "GIO2_8") (pintype "bidirectional"))
      (node (ref "U1") (pin "GND") (pinfunction "GND_GND") (pintype "bidirectional"))
      (node (ref "U2") (pin "12") (pinfunction "GND_12") (pintype "bidirectional"))
      (node (ref "U2") (pin "14") (pinfunction "GND_14") (pintype "bidirectional"))
      (node (ref "U2") (pin "8") (pinfunction "GND_8") (pintype "bidirectional"))
      (node (ref "U2") (pin "9") (pinfunction "GND_9") (pintype "bidirectional"))
      (node (ref "U2") (pin "GND") (pinfunction "GND_GND") (pintype "bidirectional"))
      (node (ref "U3") (pin "28") (pinfunction "DVSS_28") (pintype "bidirectional"))
      (node (ref "U3") (pin "7") (pinfunction "IOVSS_7") (pintype "bidirectional"))
      (node (ref "U3") (pin "GND") (pinfunction "GND_GND") (pintype "bidirectional"))
      (node (ref "U4") (pin "21") (pinfunction "GND3_21") (pintype "bidirectional"))
      (node (ref "U4") (pin "3") (pinfunction "GND1_3") (pintype "bidirectional"))
      (node (ref "U4") (pin "5") (pinfunction "GND2_5") (pintype "bidirectional"))
      (node (ref "U4") (pin "P$1") (pinfunction "GND1_P$1") (pintype "bidirectional"))
      (node (ref "U5") (pin "1") (pinfunction "GND_1") (pintype "bidirectional"))
      (node (ref "U6") (pin "1") (pinfunction "NTC_1") (pintype "bidirectional"))
      (node (ref "U6") (pin "GND") (pinfunction "GND_GND") (pintype "bidirectional"))
      (node (ref "USB") (pin "5") (pinfunction "GND_5") (pintype "bidirectional"))
      (node (ref "USB") (pin "GND1") (pinfunction "GND_GND1") (pintype "bidirectional"))
      (node (ref "USB") (pin "GND2") (pinfunction "GND_GND2") (pintype "bidirectional"))
      (node (ref "USB") (pin "GND3") (pinfunction "GND_GND3") (pintype "bidirectional"))
      (node (ref "USB") (pin "GND4") (pinfunction "GND_GND4") (pintype "bidirectional"))
      (node (ref "X1") (pin "2") (pinfunction "CASE_2") (pintype "passive"))
      (node (ref "X1") (pin "4") (pinfunction "CASE_4") (pintype "passive"))
      (node (ref "X2") (pin "GND-1") (pinfunction "CASE_GND-1") (pintype "passive"))
      (node (ref "X2") (pin "GND-2") (pinfunction "CASE_GND-2") (pintype "passive"))
    )
    (net (code "45") (name "Net-(AVR-PadA)") (class "Default")
      (node (ref "AVR") (pin "A") (pinfunction "A_A") (pintype "passive"))
      (node (ref "R14") (pin "1") (pinfunction "1_1") (pintype "passive"))
    )
    (net (code "46") (name "Net-(BATTERY-2)") (class "Default")
      (node (ref "BATTERY") (pin "1") (pinfunction "2_1") (pintype "passive"))
      (node (ref "Q1") (pin "2") (pinfunction "S_2") (pintype "passive"))
      (node (ref "U6") (pin "9") (pinfunction "BAT_9") (pintype "bidirectional"))
    )
    (net (code "47") (name "Net-(C25-Pad1)") (class "Default")
      (node (ref "C25") (pin "1") (pinfunction "1_1") (pintype "passive"))
      (node (ref "L8") (pin "2") (pinfunction "2_2") (pintype "passive"))
    )
    (net (code "48") (name "Net-(C25-Pad2)") (class "Default")
      (node (ref "C25") (pin "2") (pinfunction "2_2") (pintype "passive"))
      (node (ref "C26") (pin "1") (pinfunction "1_1") (pintype "passive"))
      (node (ref "C28") (pin "1") (pinfunction "1_1") (pintype "passive"))
      (node (ref "L10") (pin "2") (pinfunction "2_2") (pintype "passive"))
    )
    (net (code "49") (name "Net-(C26-Pad2)") (class "Default")
      (node (ref "C26") (pin "2") (pinfunction "2_2") (pintype "passive"))
      (node (ref "J1") (pin "SIG") (pinfunction "SIG_SIG") (pintype "bidirectional"))
    )
    (net (code "50") (name "Net-(C27-Pad1)") (class "Default")
      (node (ref "C27") (pin "1") (pinfunction "1_1") (pintype "passive"))
      (node (ref "L7") (pin "2") (pinfunction "2_2") (pintype "passive"))
      (node (ref "L8") (pin "1") (pinfunction "1_1") (pintype "passive"))
    )
    (net (code "51") (name "Net-(C54-Pad1)") (class "Default")
      (node (ref "C54") (pin "1") (pinfunction "1_1") (pintype "passive"))
      (node (ref "R19") (pin "1") (pinfunction "1_1") (pintype "passive"))
    )
    (net (code "52") (name "Net-(CC8531-PadA)") (class "Default")
      (node (ref "CC8531") (pin "A") (pinfunction "A_A") (pintype "passive"))
      (node (ref "R5") (pin "2") (pinfunction "2_2") (pintype "passive"))
    )
    (net (code "53") (name "Net-(CCD-Pad9)") (class "Default")
      (node (ref "CCD") (pin "9") (pinfunction "9_9") (pintype "bidirectional"))
      (node (ref "EXT") (pin "1") (pinfunction "1_1") (pintype "passive"))
    )
    (net (code "54") (name "Net-(CHARGE-PadA)") (class "Default")
      (node (ref "CHARGE") (pin "A") (pinfunction "A_A") (pintype "passive"))
      (node (ref "R18") (pin "1") (pinfunction "1_1") (pintype "passive"))
    )
    (net (code "55") (name "Net-(D1-C1)") (class "Default")
      (node (ref "D1") (pin "3") (pinfunction "C1_3") (pintype "passive"))
      (node (ref "L16") (pin "2") (pinfunction "2_2") (pintype "passive"))
    )
    (net (code "56") (name "Net-(D2-C1)") (class "Default")
      (node (ref "D2") (pin "3") (pinfunction "C1_3") (pintype "passive"))
      (node (ref "U5") (pin "3") (pinfunction "VIN_3") (pintype "bidirectional"))
    )
    (net (code "57") (name "Net-(POWER-PadA)") (class "Default")
      (node (ref "POWER") (pin "A") (pinfunction "A_A") (pintype "passive"))
      (node (ref "R3") (pin "1") (pinfunction "1_1") (pintype "passive"))
    )
    (net (code "58") (name "Net-(Q1-D)") (class "Default")
      (node (ref "C52") (pin "1") (pinfunction "1_1") (pintype "passive"))
      (node (ref "L17") (pin "2") (pinfunction "2_2") (pintype "passive"))
      (node (ref "Q1") (pin "3") (pinfunction "D_3") (pintype "passive"))
      (node (ref "SW1") (pin "3") (pinfunction "O_3") (pintype "bidirectional"))
      (node (ref "U6") (pin "10") (pinfunction "VOUT_10") (pintype "bidirectional"))
      (node (ref "U6") (pin "3") (pinfunction "VOUTS_3") (pintype "bidirectional"))
    )
    (net (code "59") (name "Net-(Q1-G)") (class "Default")
      (node (ref "Q1") (pin "1") (pinfunction "G_1") (pintype "passive"))
      (node (ref "U6") (pin "8") (pinfunction "GATE_8") (pintype "bidirectional"))
    )
    (net (code "60") (name "Net-(U1-AD0{slash}GIO7)") (class "Default")
      (node (ref "L11") (pin "2") (pinfunction "2_2") (pintype "passive"))
      (node (ref "U1") (pin "16") (pinfunction "AD0/GIO7_16") (pintype "bidirectional"))
    )
    (net (code "61") (name "Net-(U1-AD1{slash}GIO8)") (class "Default")
      (node (ref "L13") (pin "2") (pinfunction "2_2") (pintype "passive"))
      (node (ref "U1") (pin "17") (pinfunction "AD1/GIO8_17") (pintype "bidirectional"))
    )
    (net (code "62") (name "Net-(U1-AD2{slash}GIO9)") (class "Default")
      (node (ref "R7") (pin "1") (pinfunction "1_1") (pintype "passive"))
      (node (ref "U1") (pin "19") (pinfunction "AD2/GIO9_19") (pintype "bidirectional"))
    )
    (net (code "63") (name "Net-(U1-BCLK{slash}GIO5)") (class "Default")
      (node (ref "L6") (pin "2") (pinfunction "2_2") (pintype "passive"))
      (node (ref "U1") (pin "14") (pinfunction "BCLK/GIO5_14") (pintype "bidirectional"))
    )
    (net (code "64") (name "Net-(U1-DCPL)") (class "Default")
      (node (ref "C23") (pin "1") (pinfunction "1_1") (pintype "passive"))
      (node (ref "U1") (pin "39") (pinfunction "DCPL_39") (pintype "bidirectional"))
    )
    (net (code "65") (name "Net-(U1-GIO1)") (class "Default")
      (node (ref "CC1") (pin "3") (pinfunction "P$2_3") (pintype "bidirectional"))
      (node (ref "CC1") (pin "4") (pinfunction "P$2_4") (pintype "bidirectional"))
      (node (ref "U1") (pin "7") (pinfunction "GIO1_7") (pintype "bidirectional"))
    )
    (net (code "66") (name "Net-(U1-GIO3)") (class "Default")
      (node (ref "R5") (pin "1") (pinfunction "1_1") (pintype "passive"))
      (node (ref "U1") (pin "9") (pinfunction "GIO3_9") (pintype "bidirectional"))
    )
    (net (code "67") (name "Net-(U1-MCLK{slash}GIO4)") (class "Default")
      (node (ref "L5") (pin "2") (pinfunction "2_2") (pintype "passive"))
      (node (ref "U1") (pin "13") (pinfunction "MCLK/GIO4_13") (pintype "bidirectional"))
    )
    (net (code "68") (name "Net-(U1-RBIAS)") (class "Default")
      (node (ref "R4") (pin "2") (pinfunction "2_2") (pintype "passive"))
      (node (ref "U1") (pin "30") (pinfunction "RBIAS_30") (pintype "bidirectional"))
    )
    (net (code "69") (name "Net-(U1-RSTN)") (class "Default")
      (node (ref "L4") (pin "1") (pinfunction "1_1") (pintype "passive"))
      (node (ref "U1") (pin "11") (pinfunction "RSTN_11") (pintype "bidirectional"))
    )
    (net (code "70") (name "Net-(U1-USBN)") (class "Default")
      (node (ref "C14") (pin "1") (pinfunction "1_1") (pintype "passive"))
      (node (ref "R1") (pin "1") (pinfunction "1_1") (pintype "passive"))
      (node (ref "U1") (pin "1") (pinfunction "USBN_1") (pintype "bidirectional"))
    )
    (net (code "71") (name "Net-(U1-USBP)") (class "Default")
      (node (ref "C13") (pin "1") (pinfunction "1_1") (pintype "passive"))
      (node (ref "R2") (pin "1") (pinfunction "1_1") (pintype "passive"))
      (node (ref "U1") (pin "2") (pinfunction "USBP_2") (pintype "bidirectional"))
    )
    (net (code "72") (name "Net-(U1-WCLK{slash}GIO6)") (class "Default")
      (node (ref "L9") (pin "2") (pinfunction "2_2") (pintype "passive"))
      (node (ref "U1") (pin "15") (pinfunction "WCLK/GIO6_15") (pintype "bidirectional"))
    )
    (net (code "73") (name "Net-(U1-X0)") (class "Default")
      (node (ref "C24") (pin "1") (pinfunction "1_1") (pintype "passive"))
      (node (ref "U1") (pin "22") (pinfunction "X0_22") (pintype "bidirectional"))
      (node (ref "X1") (pin "3") (pinfunction "2_3") (pintype "passive"))
    )
    (net (code "74") (name "Net-(U1-X1)") (class "Default")
      (node (ref "C29") (pin "1") (pinfunction "1_1") (pintype "passive"))
      (node (ref "U1") (pin "21") (pinfunction "X1_21") (pintype "bidirectional"))
      (node (ref "X1") (pin "1") (pinfunction "1_1") (pintype "passive"))
    )
    (net (code "75") (name "Net-(U1-XPAEN)") (class "Default")
      (node (ref "L12") (pin "1") (pinfunction "1_1") (pintype "passive"))
      (node (ref "U1") (pin "36") (pinfunction "XPAEN_36") (pintype "bidirectional"))
    )
    (net (code "76") (name "Net-(U2-ANT)") (class "Default")
      (node (ref "L7") (pin "1") (pinfunction "1_1") (pintype "passive"))
      (node (ref "U2") (pin "11") (pinfunction "ANT_11") (pintype "bidirectional"))
    )
    (net (code "77") (name "Net-(U2-BIAS)") (class "Default")
      (node (ref "R8") (pin "2") (pinfunction "2_2") (pintype "passive"))
      (node (ref "U2") (pin "15") (pinfunction "BIAS_15") (pintype "bidirectional"))
    )
    (net (code "78") (name "Net-(U2-HGM)") (class "Default")
      (node (ref "R9") (pin "1") (pinfunction "1_1") (pintype "passive"))
      (node (ref "U2") (pin "7") (pinfunction "HGM_7") (pintype "bidirectional"))
    )
    (net (code "79") (name "Net-(U3-AVDD)") (class "Default")
      (node (ref "C48") (pin "1") (pinfunction "1_1") (pintype "passive"))
      (node (ref "U3") (pin "24") (pinfunction "AVDD_24") (pintype "bidirectional"))
    )
    (net (code "80") (name "Net-(U3-DVDD)") (class "Default")
      (node (ref "C49") (pin "1") (pinfunction "1_1") (pintype "passive"))
      (node (ref "U3") (pin "29") (pinfunction "DVDD_29") (pintype "bidirectional"))
    )
    (net (code "81") (name "Net-(U3-IN1_L)") (class "Default")
      (node (ref "C38") (pin "2") (pinfunction "2_2") (pintype "passive"))
      (node (ref "U3") (pin "13") (pinfunction "IN1_L_13") (pintype "bidirectional"))
    )
    (net (code "82") (name "Net-(U3-IN1_R)") (class "Default")
      (node (ref "C37") (pin "2") (pinfunction "2_2") (pintype "passive"))
      (node (ref "U3") (pin "14") (pinfunction "IN1_R_14") (pintype "bidirectional"))
    )
    (net (code "83") (name "Net-(U3-LOL)") (class "Default")
      (node (ref "R13") (pin "2") (pinfunction "2_2") (pintype "passive"))
      (node (ref "U3") (pin "22") (pinfunction "LOL_22") (pintype "bidirectional"))
    )
    (net (code "84") (name "Net-(U3-LOR)") (class "Default")
      (node (ref "R16") (pin "2") (pinfunction "2_2") (pintype "passive"))
      (node (ref "U3") (pin "23") (pinfunction "LOR_23") (pintype "bidirectional"))
    )
    (net (code "85") (name "Net-(U3-REF)") (class "Default")
      (node (ref "C50") (pin "1") (pinfunction "1_1") (pintype "passive"))
      (node (ref "U3") (pin "18") (pinfunction "REF_18") (pintype "bidirectional"))
    )
    (net (code "86") (name "Net-(U4-PB6(XTAL1))") (class "Default")
      (node (ref "C46") (pin "1") (pinfunction "1_1") (pintype "passive"))
      (node (ref "U4") (pin "7") (pinfunction "PB6(XTAL1)_7") (pintype "bidirectional"))
      (node (ref "X2") (pin "X1") (pinfunction "1_X1") (pintype "passive"))
    )
    (net (code "87") (name "Net-(U4-PB7(XTAL2))") (class "Default")
      (node (ref "C47") (pin "1") (pinfunction "1_1") (pintype "passive"))
      (node (ref "U4") (pin "8") (pinfunction "PB7(XTAL2)_8") (pintype "bidirectional"))
      (node (ref "X2") (pin "X2") (pinfunction "2_X2") (pintype "passive"))
    )
    (net (code "88") (name "Net-(U4-PD3)") (class "Default")
      (node (ref "R14") (pin "2") (pinfunction "2_2") (pintype "passive"))
      (node (ref "U4") (pin "1") (pinfunction "PD3_1") (pintype "bidirectional"))
    )
    (net (code "89") (name "Net-(U6-CLRPROG)") (class "Default")
      (node (ref "R19") (pin "2") (pinfunction "2_2") (pintype "passive"))
      (node (ref "R20") (pin "2") (pinfunction "2_2") (pintype "passive"))
      (node (ref "U6") (pin "2") (pinfunction "CLRPROG_2") (pintype "bidirectional"))
    )
    (net (code "90") (name "Net-(U6-C{slash}X)") (class "Default")
      (node (ref "R21") (pin "2") (pinfunction "2_2") (pintype "passive"))
      (node (ref "U6") (pin "5") (pinfunction "C/X_5") (pintype "bidirectional"))
      (node (ref "U6") (pin "6") (pinfunction "PROG_6") (pintype "bidirectional"))
    )
    (net (code "91") (name "Net-(U6-SW)") (class "Default")
      (node (ref "L17") (pin "1") (pinfunction "1_1") (pintype "passive"))
      (node (ref "U6") (pin "12") (pinfunction "SW_12") (pintype "bidirectional"))
    )
    (net (code "92") (name "Net-(U6-VBUS)") (class "Default")
      (node (ref "C51") (pin "1") (pinfunction "1_1") (pintype "passive"))
      (node (ref "R18") (pin "2") (pinfunction "2_2") (pintype "passive"))
      (node (ref "U6") (pin "11") (pinfunction "VBUS_11") (pintype "bidirectional"))
      (node (ref "V_CHRG") (pin "2") (pinfunction "2_2") (pintype "passive"))
    )
    (net (code "93") (name "Net-(U6-~{CHRG})") (class "Default")
      (node (ref "CHARGE") (pin "C") (pinfunction "C_C") (pintype "passive"))
      (node (ref "U6") (pin "7") (pinfunction "~{CHRG}_7") (pintype "bidirectional"))
    )
    (net (code "94") (name "Net-(U7A--IN)") (class "Default")
      (node (ref "R12") (pin "2") (pinfunction "2_2") (pintype "passive"))
      (node (ref "R13") (pin "1") (pinfunction "1_1") (pintype "passive"))
      (node (ref "U7") (pin "2") (pinfunction "-IN_2") (pintype "input"))
    )
    (net (code "95") (name "Net-(U7A-OUT)") (class "Default")
      (node (ref "C36") (pin "1") (pinfunction "1_1") (pintype "passive"))
      (node (ref "R12") (pin "1") (pinfunction "1_1") (pintype "passive"))
      (node (ref "U7") (pin "1") (pinfunction "OUT_1") (pintype "output"))
    )
    (net (code "96") (name "Net-(U7B--IN)") (class "Default")
      (node (ref "R15") (pin "2") (pinfunction "2_2") (pintype "passive"))
      (node (ref "R16") (pin "1") (pinfunction "1_1") (pintype "passive"))
      (node (ref "U7") (pin "6") (pinfunction "-IN_6") (pintype "input"))
    )
    (net (code "97") (name "Net-(U7B-OUT)") (class "Default")
      (node (ref "C39") (pin "1") (pinfunction "1_1") (pintype "passive"))
      (node (ref "R15") (pin "1") (pinfunction "1_1") (pintype "passive"))
      (node (ref "U7") (pin "7") (pinfunction "OUT_7") (pintype "output"))
    )
    (net (code "98") (name "unconnected-(CCD-Pad3)") (class "Default")
      (node (ref "CCD") (pin "3") (pinfunction "3_3") (pintype "bidirectional"))
    )
    (net (code "99") (name "unconnected-(CCD-Pad4)") (class "Default")
      (node (ref "CCD") (pin "4") (pinfunction "4_4") (pintype "bidirectional"))
    )
    (net (code "100") (name "unconnected-(SW1-A-Pad1)") (class "Default")
      (node (ref "SW1") (pin "1") (pinfunction "A_1") (pintype "bidirectional"))
    )
    (net (code "101") (name "unconnected-(U1-SCL{slash}GIO10-Pad32)") (class "Default")
      (node (ref "U1") (pin "32") (pinfunction "SCL/GIO10_32") (pintype "bidirectional"))
    )
    (net (code "102") (name "unconnected-(U1-SDA{slash}GIO11-Pad33)") (class "Default")
      (node (ref "U1") (pin "33") (pinfunction "SDA/GIO11_33") (pintype "bidirectional"))
    )
    (net (code "103") (name "unconnected-(U2-RXTX-Pad3)") (class "Default")
      (node (ref "U2") (pin "3") (pinfunction "RXTX_3") (pintype "bidirectional"))
    )
    (net (code "104") (name "unconnected-(U3-GPIO{slash}MFP5-Pad32)") (class "Default")
      (node (ref "U3") (pin "32") (pinfunction "GPIO/MFP5_32") (pintype "bidirectional"))
    )
    (net (code "105") (name "unconnected-(U3-HPL-Pad25)") (class "Default")
      (node (ref "U3") (pin "25") (pinfunction "HPL_25") (pintype "bidirectional"))
    )
    (net (code "106") (name "unconnected-(U3-HPR-Pad27)") (class "Default")
      (node (ref "U3") (pin "27") (pinfunction "HPR_27") (pintype "bidirectional"))
    )
    (net (code "107") (name "unconnected-(U3-IN2_L-Pad15)") (class "Default")
      (node (ref "U3") (pin "15") (pinfunction "IN2_L_15") (pintype "bidirectional"))
    )
    (net (code "108") (name "unconnected-(U3-IN2_R-Pad16)") (class "Default")
      (node (ref "U3") (pin "16") (pinfunction "IN2_R_16") (pintype "bidirectional"))
    )
    (net (code "109") (name "unconnected-(U3-IN3_L-Pad20)") (class "Default")
      (node (ref "U3") (pin "20") (pinfunction "IN3_L_20") (pintype "bidirectional"))
    )
    (net (code "110") (name "unconnected-(U3-IN3_R-Pad21)") (class "Default")
      (node (ref "U3") (pin "21") (pinfunction "IN3_R_21") (pintype "bidirectional"))
    )
    (net (code "111") (name "unconnected-(U3-MICBIAS-Pad19)") (class "Default")
      (node (ref "U3") (pin "19") (pinfunction "MICBIAS_19") (pintype "bidirectional"))
    )
    (net (code "112") (name "unconnected-(U4-ADC6-Pad19)") (class "Default")
      (node (ref "U4") (pin "19") (pinfunction "ADC6_19") (pintype "bidirectional"))
    )
    (net (code "113") (name "unconnected-(U4-ADC7-Pad22)") (class "Default")
      (node (ref "U4") (pin "22") (pinfunction "ADC7_22") (pintype "bidirectional"))
    )
    (net (code "114") (name "unconnected-(U4-AREF-Pad20)") (class "Default")
      (node (ref "U4") (pin "20") (pinfunction "AREF_20") (pintype "bidirectional"))
    )
    (net (code "115") (name "unconnected-(U4-PB1-Pad13)") (class "Default")
      (node (ref "U4") (pin "13") (pinfunction "PB1_13") (pintype "bidirectional"))
    )
    (net (code "116") (name "unconnected-(U4-PB2(~{SS})-Pad14)") (class "Default")
      (node (ref "U4") (pin "14") (pinfunction "PB2(~{SS})_14") (pintype "bidirectional"))
    )
    (net (code "117") (name "unconnected-(U4-PD4(XCK)-Pad2)") (class "Default")
      (node (ref "U4") (pin "2") (pinfunction "PD4(XCK)_2") (pintype "bidirectional"))
    )
    (net (code "118") (name "unconnected-(USB-ID-Pad4)") (class "Default")
      (node (ref "USB") (pin "4") (pinfunction "ID_4") (pintype "bidirectional"))
    )
  )
)
